# Earthnet.net
KiCad netlist of a schematic drawn in Altium Designer
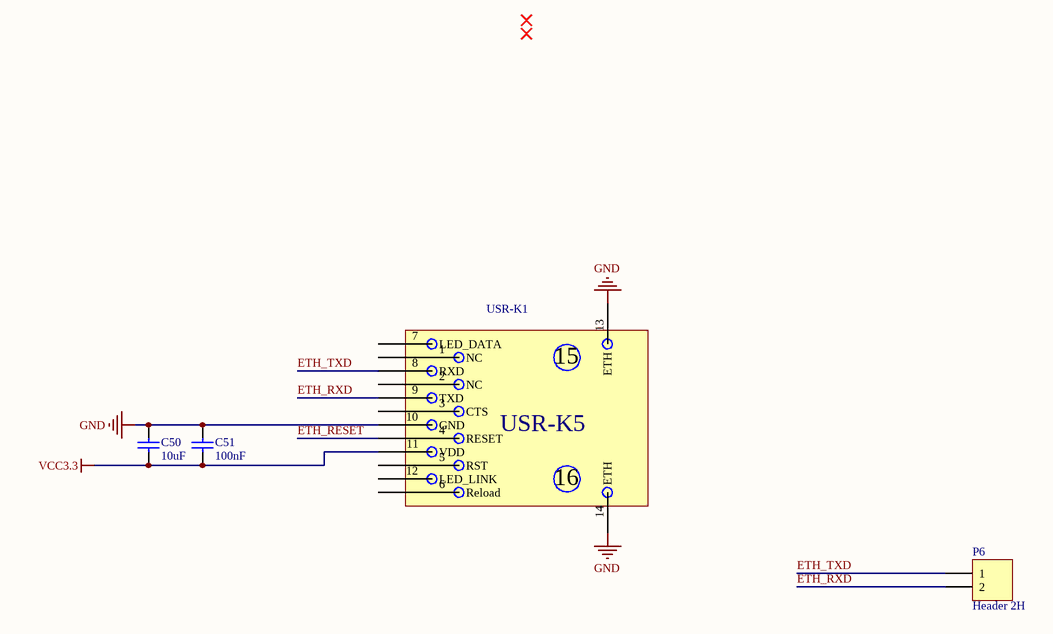
[diagram p0: Earthnet.SchDoc]

(export (version "E")
  (design (tool "Eeschema 10.0.6"))
  (components
    (comp (ref "C50")
      (value "10uF")
      (footprint "C 0603_M")
      (description "10uF/6V3/10%")
      (fields (field (name "PUBLISHER") "Altium Limited"))
      (libsource (lib "Miscellaneous Devices") (part "Cap"))
    )
    (comp (ref "C51")
      (value "100nF")
      (footprint "C 0603_M")
      (description "100nF/50V/10%")
      (fields (field (name "PUBLISHER") "Altium Limited"))
      (libsource (lib "Miscellaneous Devices") (part "Cap"))
    )
    (comp (ref "P6")
      (value "Header 2H")
      (footprint "HDR2.54-LI-2P")
      (description "Header, 2-Pin, Right Angle")
      (fields (field (name "PUBLISHER") "Altium Limited"))
      (libsource (lib "baseboard") (part "Header 2H"))
    )
    (comp (ref "USR-K1")
      (value "USR-K5")
      (footprint "USR-K3 V2")
      (libsource (lib "baseboard") (part "USR-K5"))
    )
  )
  (nets
    (net (code "1") (name "/ETH_RESET") (class "Default")
      (node (ref "USR-K1") (pin "4") (pinfunction "RESET_4") (pintype "passive"))
    )
    (net (code "2") (name "/ETH_RXD") (class "Default")
      (node (ref "P6") (pin "2") (pinfunction "2_2") (pintype "passive"))
      (node (ref "USR-K1") (pin "9") (pinfunction "TXD_9") (pintype "passive"))
    )
    (net (code "3") (name "/ETH_TXD") (class "Default")
      (node (ref "P6") (pin "1") (pinfunction "1_1") (pintype "passive"))
      (node (ref "USR-K1") (pin "8") (pinfunction "RXD_8") (pintype "passive"))
    )
    (net (code "4") (name "GND") (class "Default")
      (node (ref "C50") (pin "2") (pinfunction "2_2") (pintype "passive"))
      (node (ref "C51") (pin "2") (pinfunction "2_2") (pintype "passive"))
      (node (ref "USR-K1") (pin "10") (pinfunction "GND_10") (pintype "passive"))
      (node (ref "USR-K1") (pin "13") (pinfunction "ETH_13") (pintype "passive"))
      (node (ref "USR-K1") (pin "14") (pinfunction "ETH_14") (pintype "passive"))
    )
    (net (code "5") (name "VCC3.3") (class "Default")
      (node (ref "C50") (pin "1") (pinfunction "1_1") (pintype "passive"))
      (node (ref "C51") (pin "1") (pinfunction "1_1") (pintype "passive"))
      (node (ref "USR-K1") (pin "11") (pinfunction "VDD_11") (pintype "passive"))
    )
    (net (code "6") (name "unconnected-(USR-K1-CTS-Pad3)") (class "Default")
      (node (ref "USR-K1") (pin "3") (pinfunction "CTS_3") (pintype "passive"))
    )
    (net (code "7") (name "unconnected-(USR-K1-LED_DATA-Pad7)") (class "Default")
      (node (ref "USR-K1") (pin "7") (pinfunction "LED_DATA_7") (pintype "passive"))
    )
    (net (code "8") (name "unconnected-(USR-K1-LED_LINK-Pad12)") (class "Default")
      (node (ref "USR-K1") (pin "12") (pinfunction "LED_LINK_12") (pintype "passive"))
    )
    (net (code "9") (name "unconnected-(USR-K1-NC-Pad1)") (class "Default")
      (node (ref "USR-K1") (pin "1") (pinfunction "NC_1") (pintype "passive"))
    )
    (net (code "10") (name "unconnected-(USR-K1-NC-Pad2)") (class "Default")
      (node (ref "USR-K1") (pin "2") (pinfunction "NC_2") (pintype "passive"))
    )
    (net (code "11") (name "unconnected-(USR-K1-RST-Pad5)") (class "Default")
      (node (ref "USR-K1") (pin "5") (pinfunction "RST_5") (pintype "passive"))
    )
    (net (code "12") (name "unconnected-(USR-K1-Reload-Pad6)") (class "Default")
      (node (ref "USR-K1") (pin "6") (pinfunction "Reload_6") (pintype "passive"))
    )
  )
)
